# mcu.net
KiCad netlist of a schematic drawn in Altium Designer
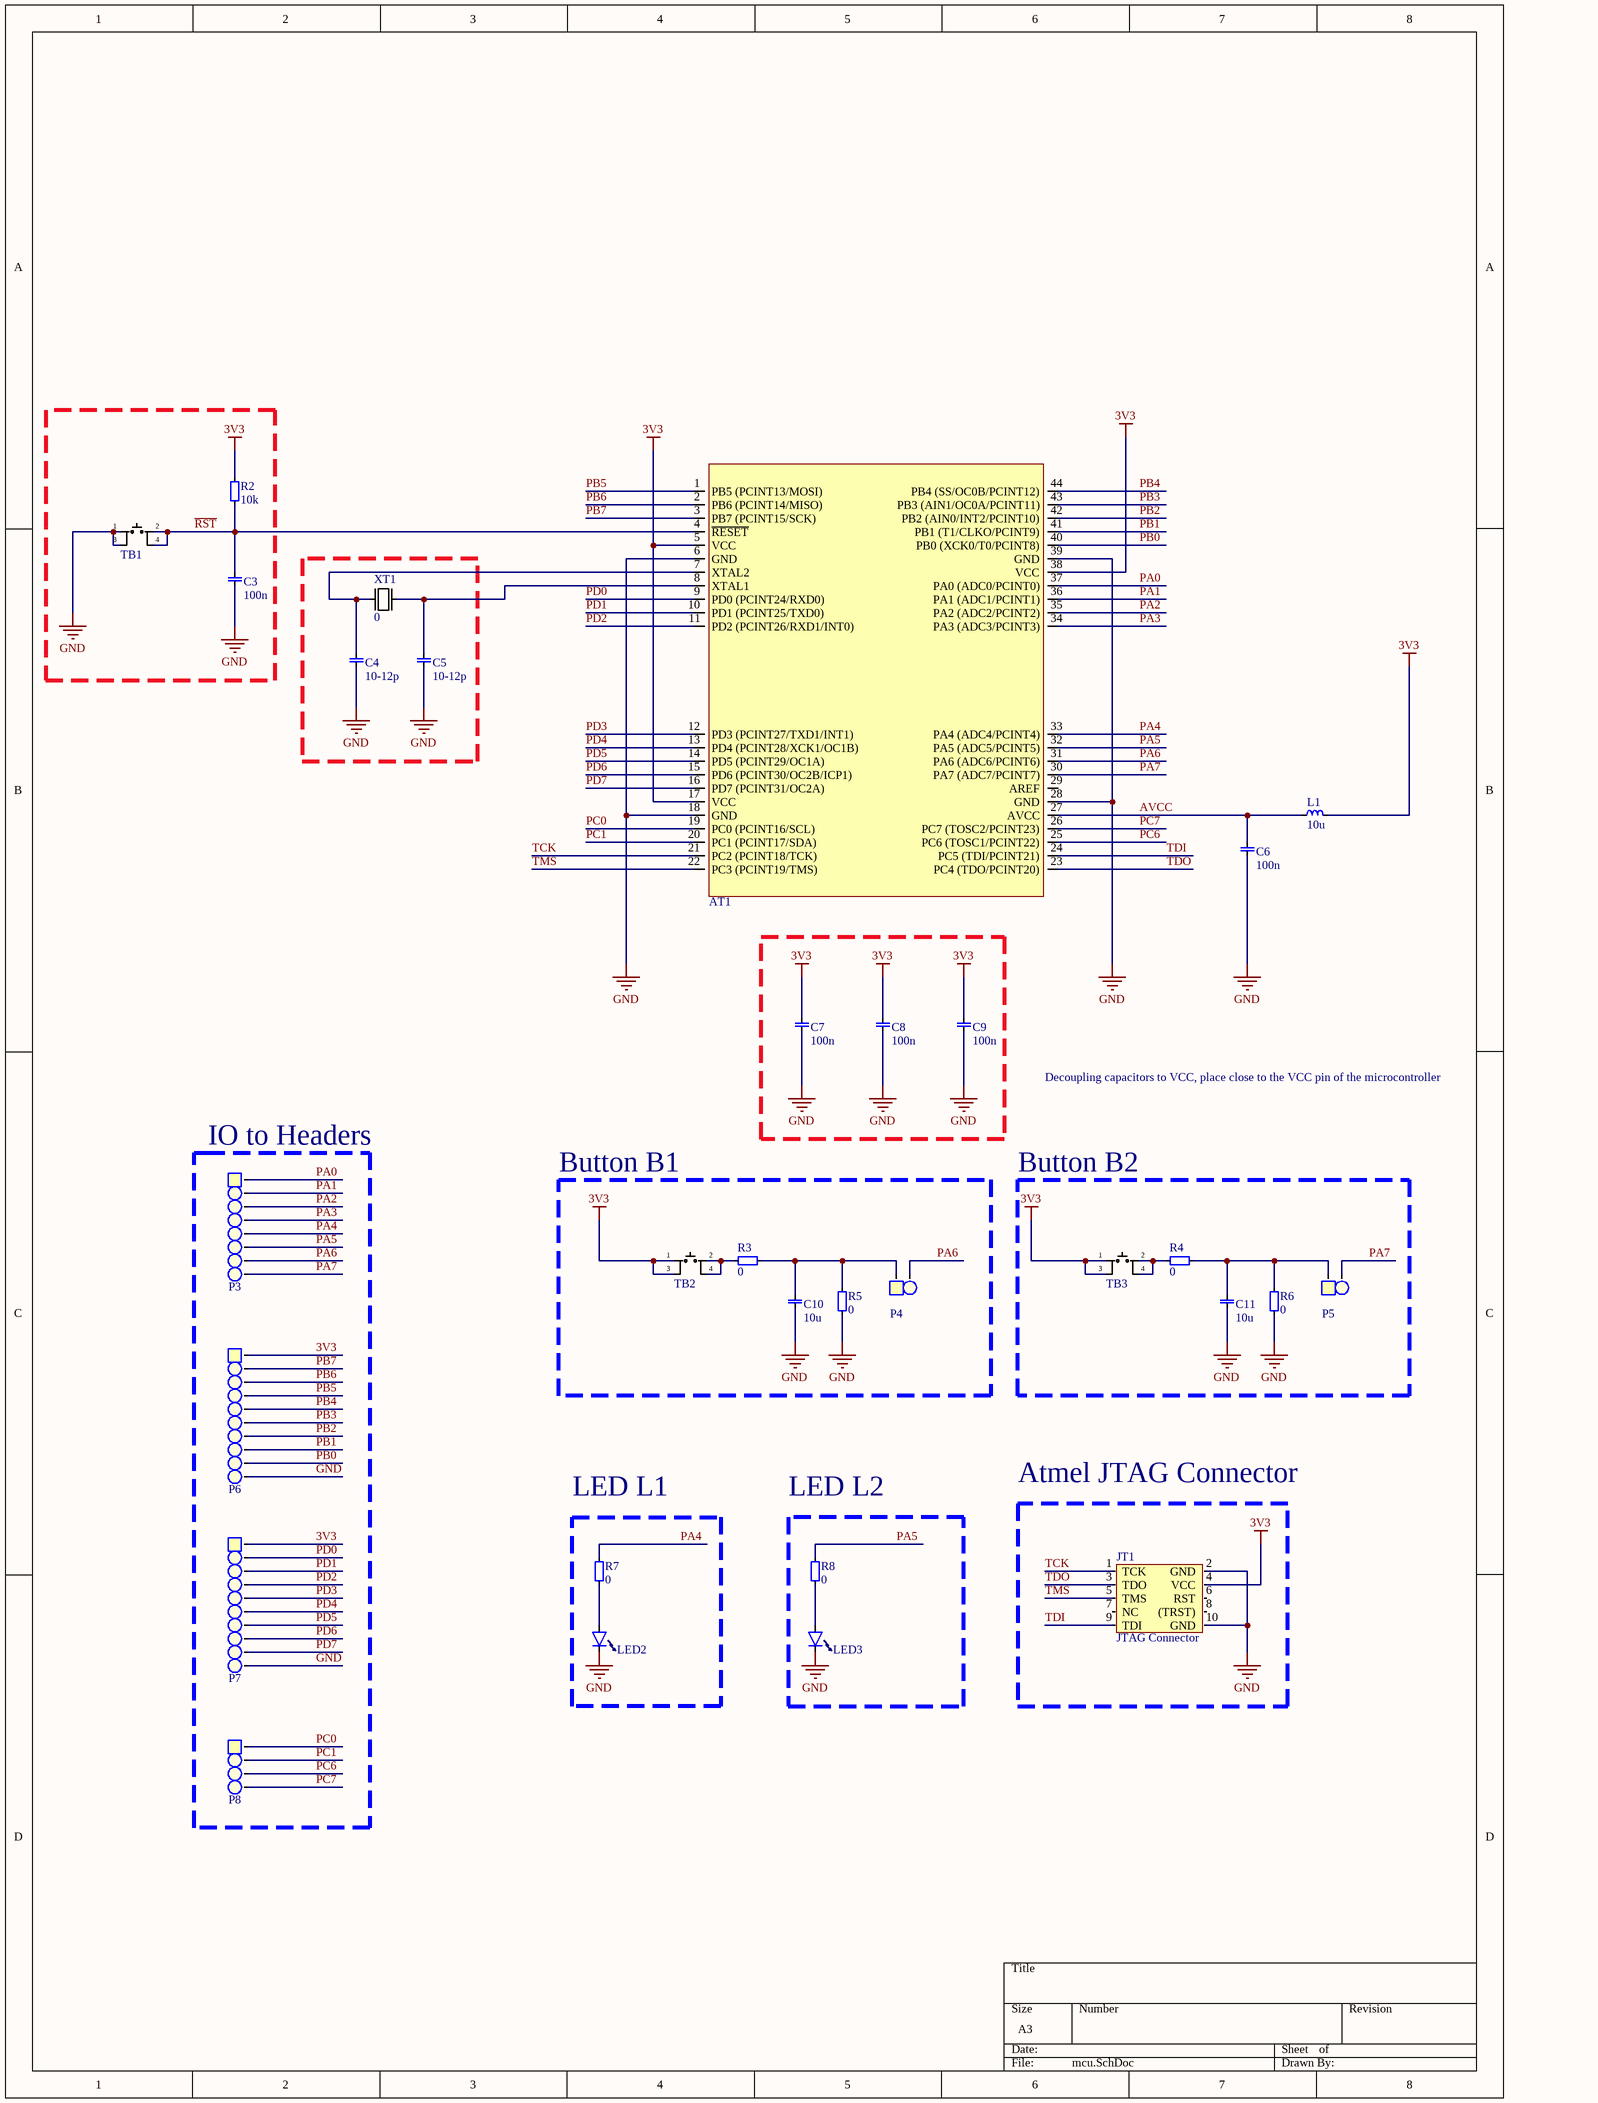
[diagram p0: mcu.SchDoc]

(export (version "E")
  (design (tool "Eeschema 10.0.6"))
  (components
    (comp (ref "AT1")
      (value "ATmega644PA")
      (footprint "TQFP-44")
      (description "ATmega644PA - Small but big and PicoPower")
      (libsource (lib "eitp15_lab1_lib") (part "ATmega644PA"))
    )
    (comp (ref "C3")
      (value "100n")
      (footprint "1206, capasitor")
      (fields (field (name "Comment") "1206, capacitor"))
      (libsource (lib "eitp15_lab1_lib") (part "1206, capacitor"))
    )
    (comp (ref "C4")
      (value "10-12p")
      (footprint "1206, capasitor")
      (fields (field (name "Comment") "1206, capacitor"))
      (libsource (lib "eitp15_lab1_lib") (part "1206, capacitor"))
    )
    (comp (ref "C5")
      (value "10-12p")
      (footprint "1206, capasitor")
      (fields (field (name "Comment") "1206, capacitor"))
      (libsource (lib "eitp15_lab1_lib") (part "1206, capacitor"))
    )
    (comp (ref "C6")
      (value "100n")
      (footprint "1206, capasitor")
      (fields (field (name "Comment") "1206, capacitor"))
      (libsource (lib "eitp15_lab1_lib") (part "1206, capacitor"))
    )
    (comp (ref "C7")
      (value "100n")
      (footprint "1206, capasitor")
      (fields (field (name "Comment") "1206, capacitor"))
      (libsource (lib "eitp15_lab1_lib") (part "1206, capacitor"))
    )
    (comp (ref "C8")
      (value "100n")
      (footprint "1206, capasitor")
      (fields (field (name "Comment") "1206, capacitor"))
      (libsource (lib "eitp15_lab1_lib") (part "1206, capacitor"))
    )
    (comp (ref "C9")
      (value "100n")
      (footprint "1206, capasitor")
      (fields (field (name "Comment") "1206, capacitor"))
      (libsource (lib "eitp15_lab1_lib") (part "1206, capacitor"))
    )
    (comp (ref "C10")
      (value "10u")
      (footprint "1206, capasitor")
      (fields (field (name "Comment") "1206, capacitor"))
      (libsource (lib "eitp15_lab1_lib") (part "1206, capacitor"))
    )
    (comp (ref "C11")
      (value "10u")
      (footprint "1206, capasitor")
      (fields (field (name "Comment") "1206, capacitor"))
      (libsource (lib "eitp15_lab1_lib") (part "1206, capacitor"))
    )
    (comp (ref "JT1")
      (value "JTAG Connector")
      (footprint "Atmel_JTAG")
      (description "Atmel JTAG Connector")
      (libsource (lib "eitp15_lab1_lib") (part "Atmel JTAG"))
    )
    (comp (ref "L1")
      (value "10u")
      (footprint "1812, coil")
      (fields (field (name "Comment") "Coil"))
      (libsource (lib "eitp15_lab1_lib") (part "Coil"))
    )
    (comp (ref "LED2")
      (value "0805, LED")
      (footprint "0805_led")
      (libsource (lib "eitp15_lab1_lib") (part "0805, LED"))
    )
    (comp (ref "LED3")
      (value "0805, LED")
      (footprint "0805_led")
      (libsource (lib "eitp15_lab1_lib") (part "0805, LED"))
    )
    (comp (ref "P3")
      (value "1x8 Pin Header")
      (footprint "1x8HEADER")
      (description "2.54 mm, TH")
      (libsource (lib "eitp15_lab1_lib") (part "1x8 Pin Header"))
    )
    (comp (ref "P4")
      (value "1x2 Pin Header")
      (footprint "1x2HEADER")
      (description "2.54 mm, TH")
      (libsource (lib "eitp15_lab1_lib") (part "1x2 Pin Header"))
    )
    (comp (ref "P5")
      (value "1x2 Pin Header")
      (footprint "1x2HEADER")
      (description "2.54 mm, TH")
      (libsource (lib "eitp15_lab1_lib") (part "1x2 Pin Header"))
    )
    (comp (ref "P6")
      (value "1x10 Pin Header")
      (footprint "1x10HEADER")
      (description "2.54 mm, TH")
      (libsource (lib "eitp15_lab1_lib") (part "1x10 Pin Header"))
    )
    (comp (ref "P7")
      (value "1x10 Pin Header")
      (footprint "1x10HEADER")
      (description "2.54 mm, TH")
      (libsource (lib "eitp15_lab1_lib") (part "1x10 Pin Header"))
    )
    (comp (ref "P8")
      (value "1x4 Pin Header")
      (footprint "1x4HEADER")
      (description "2.54 mm, TH")
      (libsource (lib "eitp15_lab1_lib") (part "1x4 Pin Header"))
    )
    (comp (ref "R2")
      (value "10k")
      (footprint "1206")
      (description "Resistor")
      (fields (field (name "Comment") "1206, resistor"))
      (libsource (lib "eitp15_lab1_lib") (part "1206, resistor"))
    )
    (comp (ref "R3")
      (value "0")
      (footprint "1206")
      (description "Resistor")
      (fields (field (name "Comment") "1206, resistor"))
      (libsource (lib "eitp15_lab1_lib") (part "1206, resistor"))
    )
    (comp (ref "R4")
      (value "0")
      (footprint "1206")
      (description "Resistor")
      (fields (field (name "Comment") "1206, resistor"))
      (libsource (lib "eitp15_lab1_lib") (part "1206, resistor"))
    )
    (comp (ref "R5")
      (value "0")
      (footprint "1206")
      (description "Resistor")
      (fields (field (name "Comment") "1206, resistor"))
      (libsource (lib "eitp15_lab1_lib") (part "1206, resistor"))
    )
    (comp (ref "R6")
      (value "0")
      (footprint "1206")
      (description "Resistor")
      (fields (field (name "Comment") "1206, resistor"))
      (libsource (lib "eitp15_lab1_lib") (part "1206, resistor"))
    )
    (comp (ref "R7")
      (value "0")
      (footprint "1206")
      (description "Resistor")
      (fields (field (name "Comment") "1206, resistor"))
      (libsource (lib "eitp15_lab1_lib") (part "1206, resistor"))
    )
    (comp (ref "R8")
      (value "0")
      (footprint "1206")
      (description "Resistor")
      (fields (field (name "Comment") "1206, resistor"))
      (libsource (lib "eitp15_lab1_lib") (part "1206, resistor"))
    )
    (comp (ref "TB1")
      (value "Tactile Button")
      (footprint "Button smd")
      (description "Tactile Switch Small Low")
      (libsource (lib "eitp15_lab1_lib") (part "Button SMD"))
    )
    (comp (ref "TB2")
      (value "Tactile Button")
      (footprint "Button smd")
      (description "Tactile Switch Small Low")
      (libsource (lib "eitp15_lab1_lib") (part "Button SMD"))
    )
    (comp (ref "TB3")
      (value "Tactile Button")
      (footprint "Button smd")
      (description "Tactile Switch Small Low")
      (libsource (lib "eitp15_lab1_lib") (part "Button SMD"))
    )
    (comp (ref "XT1")
      (value "0")
      (footprint "XTAL_SMD_LP")
      (description "16 MHz, SMD, 5mm x 3,2mm, 30 ppm")
      (fields (field (name "Comment") "XTAL TXC 7A"))
      (libsource (lib "eitp15_lab1_lib") (part "XTAL TXC 7A"))
    )
  )
  (nets
    (net (code "1") (name "/AVCC") (class "Default")
      (node (ref "AT1") (pin "27") (pinfunction "AVCC_27") (pintype "passive"))
      (node (ref "C6") (pin "1") (pinfunction "1_1") (pintype "passive"))
      (node (ref "L1") (pin "2") (pinfunction "2_2") (pintype "passive"))
    )
    (net (code "2") (name "/PA0") (class "Default")
      (node (ref "AT1") (pin "37") (pinfunction "PA0_(ADC0/PCINT0)_37") (pintype "passive"))
      (node (ref "P3") (pin "1") (pinfunction "1_1") (pintype "passive"))
    )
    (net (code "3") (name "/PA1") (class "Default")
      (node (ref "AT1") (pin "36") (pinfunction "PA1_(ADC1/PCINT1)_36") (pintype "passive"))
      (node (ref "P3") (pin "2") (pinfunction "2_2") (pintype "passive"))
    )
    (net (code "4") (name "/PA2") (class "Default")
      (node (ref "AT1") (pin "35") (pinfunction "PA2_(ADC2/PCINT2)_35") (pintype "passive"))
      (node (ref "P3") (pin "3") (pinfunction "3_3") (pintype "passive"))
    )
    (net (code "5") (name "/PA3") (class "Default")
      (node (ref "AT1") (pin "34") (pinfunction "PA3_(ADC3/PCINT3)_34") (pintype "passive"))
      (node (ref "P3") (pin "4") (pinfunction "4_4") (pintype "passive"))
    )
    (net (code "6") (name "/PA4") (class "Default")
      (node (ref "AT1") (pin "33") (pinfunction "PA4_(ADC4/PCINT4)_33") (pintype "passive"))
      (node (ref "P3") (pin "5") (pinfunction "5_5") (pintype "passive"))
      (node (ref "R7") (pin "0") (pinfunction "0_0") (pintype "passive"))
    )
    (net (code "7") (name "/PA5") (class "Default")
      (node (ref "AT1") (pin "32") (pinfunction "PA5_(ADC5/PCINT5)_32") (pintype "passive"))
      (node (ref "P3") (pin "6") (pinfunction "6_6") (pintype "passive"))
      (node (ref "R8") (pin "0") (pinfunction "0_0") (pintype "passive"))
    )
    (net (code "8") (name "/PA6") (class "Default")
      (node (ref "AT1") (pin "31") (pinfunction "PA6_(ADC6/PCINT6)_31") (pintype "passive"))
      (node (ref "P3") (pin "7") (pinfunction "7_7") (pintype "passive"))
      (node (ref "P4") (pin "2") (pinfunction "2_2") (pintype "passive"))
    )
    (net (code "9") (name "/PA7") (class "Default")
      (node (ref "AT1") (pin "30") (pinfunction "PA7_(ADC7/PCINT7)_30") (pintype "passive"))
      (node (ref "P3") (pin "8") (pinfunction "8_8") (pintype "passive"))
      (node (ref "P5") (pin "2") (pinfunction "2_2") (pintype "passive"))
    )
    (net (code "10") (name "/PB0") (class "Default")
      (node (ref "AT1") (pin "40") (pinfunction "PB0_(XCK0/T0/PCINT8)_40") (pintype "passive"))
      (node (ref "P6") (pin "9") (pinfunction "9_9") (pintype "passive"))
    )
    (net (code "11") (name "/PB1") (class "Default")
      (node (ref "AT1") (pin "41") (pinfunction "PB1_(T1/CLKO/PCINT9)_41") (pintype "passive"))
      (node (ref "P6") (pin "8") (pinfunction "8_8") (pintype "passive"))
    )
    (net (code "12") (name "/PB2") (class "Default")
      (node (ref "AT1") (pin "42") (pinfunction "PB2_(AIN0/INT2/PCINT10)_42") (pintype "passive"))
      (node (ref "P6") (pin "7") (pinfunction "7_7") (pintype "passive"))
    )
    (net (code "13") (name "/PB3") (class "Default")
      (node (ref "AT1") (pin "43") (pinfunction "PB3_(AIN1/OC0A/PCINT11)_43") (pintype "passive"))
      (node (ref "P6") (pin "6") (pinfunction "6_6") (pintype "passive"))
    )
    (net (code "14") (name "/PB4") (class "Default")
      (node (ref "AT1") (pin "44") (pinfunction "PB4_(SS/OC0B/PCINT12)_44") (pintype "passive"))
      (node (ref "P6") (pin "5") (pinfunction "5_5") (pintype "passive"))
    )
    (net (code "15") (name "/PB5") (class "Default")
      (node (ref "AT1") (pin "1") (pinfunction "PB5_(PCINT13/MOSI)_1") (pintype "passive"))
      (node (ref "P6") (pin "4") (pinfunction "4_4") (pintype "passive"))
    )
    (net (code "16") (name "/PB6") (class "Default")
      (node (ref "AT1") (pin "2") (pinfunction "PB6_(PCINT14/MISO)_2") (pintype "passive"))
      (node (ref "P6") (pin "3") (pinfunction "3_3") (pintype "passive"))
    )
    (net (code "17") (name "/PB7") (class "Default")
      (node (ref "AT1") (pin "3") (pinfunction "PB7_(PCINT15/SCK)_3") (pintype "passive"))
      (node (ref "P6") (pin "2") (pinfunction "2_2") (pintype "passive"))
    )
    (net (code "18") (name "/PC0") (class "Default")
      (node (ref "AT1") (pin "19") (pinfunction "PC0_(PCINT16/SCL)_19") (pintype "passive"))
      (node (ref "P8") (pin "1") (pinfunction "1_1") (pintype "passive"))
    )
    (net (code "19") (name "/PC1") (class "Default")
      (node (ref "AT1") (pin "20") (pinfunction "PC1_(PCINT17/SDA)_20") (pintype "passive"))
      (node (ref "P8") (pin "2") (pinfunction "2_2") (pintype "passive"))
    )
    (net (code "20") (name "/PC6") (class "Default")
      (node (ref "AT1") (pin "25") (pinfunction "PC6_(TOSC1/PCINT22)_25") (pintype "passive"))
      (node (ref "P8") (pin "3") (pinfunction "3_3") (pintype "passive"))
    )
    (net (code "21") (name "/PC7") (class "Default")
      (node (ref "AT1") (pin "26") (pinfunction "PC7_(TOSC2/PCINT23)_26") (pintype "passive"))
      (node (ref "P8") (pin "4") (pinfunction "4_4") (pintype "passive"))
    )
    (net (code "22") (name "/PD0") (class "Default")
      (node (ref "AT1") (pin "9") (pinfunction "PD0_(PCINT24/RXD0)_9") (pintype "passive"))
      (node (ref "P7") (pin "2") (pinfunction "2_2") (pintype "passive"))
    )
    (net (code "23") (name "/PD1") (class "Default")
      (node (ref "AT1") (pin "10") (pinfunction "PD1_(PCINT25/TXD0)_10") (pintype "passive"))
      (node (ref "P7") (pin "3") (pinfunction "3_3") (pintype "passive"))
    )
    (net (code "24") (name "/PD2") (class "Default")
      (node (ref "AT1") (pin "11") (pinfunction "PD2_(PCINT26/RXD1/INT0)_11") (pintype "passive"))
      (node (ref "P7") (pin "4") (pinfunction "4_4") (pintype "passive"))
    )
    (net (code "25") (name "/PD3") (class "Default")
      (node (ref "AT1") (pin "12") (pinfunction "PD3_(PCINT27/TXD1/INT1)_12") (pintype "passive"))
      (node (ref "P7") (pin "5") (pinfunction "5_5") (pintype "passive"))
    )
    (net (code "26") (name "/PD4") (class "Default")
      (node (ref "AT1") (pin "13") (pinfunction "PD4_(PCINT28/XCK1/OC1B)_13") (pintype "passive"))
      (node (ref "P7") (pin "6") (pinfunction "6_6") (pintype "passive"))
    )
    (net (code "27") (name "/PD5") (class "Default")
      (node (ref "AT1") (pin "14") (pinfunction "PD5_(PCINT29/OC1A)_14") (pintype "passive"))
      (node (ref "P7") (pin "7") (pinfunction "7_7") (pintype "passive"))
    )
    (net (code "28") (name "/PD6") (class "Default")
      (node (ref "AT1") (pin "15") (pinfunction "PD6_(PCINT30/OC2B/ICP1)_15") (pintype "passive"))
      (node (ref "P7") (pin "8") (pinfunction "8_8") (pintype "passive"))
    )
    (net (code "29") (name "/PD7") (class "Default")
      (node (ref "AT1") (pin "16") (pinfunction "PD7_(PCINT31/OC2A)_16") (pintype "passive"))
      (node (ref "P7") (pin "9") (pinfunction "9_9") (pintype "passive"))
    )
    (net (code "30") (name "/TCK") (class "Default")
      (node (ref "AT1") (pin "21") (pinfunction "PC2_(PCINT18/TCK)_21") (pintype "passive"))
      (node (ref "JT1") (pin "1") (pinfunction "TCK_1") (pintype "passive"))
    )
    (net (code "31") (name "/TDI") (class "Default")
      (node (ref "AT1") (pin "24") (pinfunction "PC5_(TDI/PCINT21)_24") (pintype "passive"))
      (node (ref "JT1") (pin "9") (pinfunction "TDI_9") (pintype "passive"))
    )
    (net (code "32") (name "/TDO") (class "Default")
      (node (ref "AT1") (pin "23") (pinfunction "PC4_(TDO/PCINT20)_23") (pintype "passive"))
      (node (ref "JT1") (pin "3") (pinfunction "TDO_3") (pintype "passive"))
    )
    (net (code "33") (name "/TMS") (class "Default")
      (node (ref "AT1") (pin "22") (pinfunction "PC3_(PCINT19/TMS)_22") (pintype "passive"))
      (node (ref "JT1") (pin "5") (pinfunction "TMS_5") (pintype "passive"))
    )
    (net (code "34") (name "/~{RST}") (class "Default")
      (node (ref "AT1") (pin "4") (pinfunction "~{RESET}_4") (pintype "passive"))
      (node (ref "C3") (pin "1") (pinfunction "1_1") (pintype "passive"))
      (node (ref "R2") (pin "1") (pinfunction "1_1") (pintype "passive"))
      (node (ref "TB1") (pin "2") (pinfunction "2_2") (pintype "passive"))
      (node (ref "TB1") (pin "4") (pinfunction "4_4") (pintype "passive"))
    )
    (net (code "35") (name "3V3") (class "Default")
      (node (ref "AT1") (pin "17") (pinfunction "VCC_17") (pintype "passive"))
      (node (ref "AT1") (pin "38") (pinfunction "VCC_38") (pintype "passive"))
      (node (ref "AT1") (pin "5") (pinfunction "VCC_5") (pintype "passive"))
      (node (ref "C7") (pin "1") (pinfunction "1_1") (pintype "passive"))
      (node (ref "C8") (pin "1") (pinfunction "1_1") (pintype "passive"))
      (node (ref "C9") (pin "1") (pinfunction "1_1") (pintype "passive"))
      (node (ref "JT1") (pin "4") (pinfunction "VCC_4") (pintype "passive"))
      (node (ref "L1") (pin "1") (pinfunction "1_1") (pintype "passive"))
      (node (ref "P6") (pin "1") (pinfunction "1_1") (pintype "passive"))
      (node (ref "P7") (pin "1") (pinfunction "1_1") (pintype "passive"))
      (node (ref "R2") (pin "0") (pinfunction "0_0") (pintype "passive"))
      (node (ref "TB2") (pin "1") (pinfunction "1_1") (pintype "passive"))
      (node (ref "TB2") (pin "3") (pinfunction "3_3") (pintype "passive"))
      (node (ref "TB3") (pin "1") (pinfunction "1_1") (pintype "passive"))
      (node (ref "TB3") (pin "3") (pinfunction "3_3") (pintype "passive"))
    )
    (net (code "36") (name "GND") (class "Default")
      (node (ref "AT1") (pin "18") (pinfunction "GND_18") (pintype "passive"))
      (node (ref "AT1") (pin "28") (pinfunction "GND_28") (pintype "passive"))
      (node (ref "AT1") (pin "39") (pinfunction "GND_39") (pintype "passive"))
      (node (ref "AT1") (pin "6") (pinfunction "GND_6") (pintype "passive"))
      (node (ref "C10") (pin "0") (pinfunction "0_0") (pintype "passive"))
      (node (ref "C11") (pin "0") (pinfunction "0_0") (pintype "passive"))
      (node (ref "C3") (pin "0") (pinfunction "0_0") (pintype "passive"))
      (node (ref "C4") (pin "0") (pinfunction "0_0") (pintype "passive"))
      (node (ref "C5") (pin "0") (pinfunction "0_0") (pintype "passive"))
      (node (ref "C6") (pin "0") (pinfunction "0_0") (pintype "passive"))
      (node (ref "C7") (pin "0") (pinfunction "0_0") (pintype "passive"))
      (node (ref "C8") (pin "0") (pinfunction "0_0") (pintype "passive"))
      (node (ref "C9") (pin "0") (pinfunction "0_0") (pintype "passive"))
      (node (ref "JT1") (pin "10") (pinfunction "GND_10") (pintype "passive"))
      (node (ref "JT1") (pin "2") (pinfunction "GND_2") (pintype "passive"))
      (node (ref "LED2") (pin "0") (pinfunction "Cathode_0") (pintype "passive"))
      (node (ref "LED3") (pin "0") (pinfunction "Cathode_0") (pintype "passive"))
      (node (ref "P6") (pin "10") (pinfunction "10_10") (pintype "passive"))
      (node (ref "P7") (pin "10") (pinfunction "10_10") (pintype "passive"))
      (node (ref "R5") (pin "1") (pinfunction "1_1") (pintype "passive"))
      (node (ref "R6") (pin "1") (pinfunction "1_1") (pintype "passive"))
      (node (ref "TB1") (pin "1") (pinfunction "1_1") (pintype "passive"))
      (node (ref "TB1") (pin "3") (pinfunction "3_3") (pintype "passive"))
    )
    (net (code "37") (name "Net-(AT1-XTAL1)") (class "Default")
      (node (ref "AT1") (pin "8") (pinfunction "XTAL1_8") (pintype "passive"))
      (node (ref "C5") (pin "1") (pinfunction "1_1") (pintype "passive"))
      (node (ref "XT1") (pin "2") (pinfunction "2_2") (pintype "passive"))
    )
    (net (code "38") (name "Net-(AT1-XTAL2)") (class "Default")
      (node (ref "AT1") (pin "7") (pinfunction "XTAL2_7") (pintype "passive"))
      (node (ref "C4") (pin "1") (pinfunction "1_1") (pintype "passive"))
      (node (ref "XT1") (pin "1") (pinfunction "1_1") (pintype "passive"))
    )
    (net (code "39") (name "Net-(C10-Pad1)") (class "Default")
      (node (ref "C10") (pin "1") (pinfunction "1_1") (pintype "passive"))
      (node (ref "P4") (pin "1") (pinfunction "1_1") (pintype "passive"))
      (node (ref "R3") (pin "0") (pinfunction "0_0") (pintype "passive"))
      (node (ref "R5") (pin "0") (pinfunction "0_0") (pintype "passive"))
    )
    (net (code "40") (name "Net-(C11-Pad1)") (class "Default")
      (node (ref "C11") (pin "1") (pinfunction "1_1") (pintype "passive"))
      (node (ref "P5") (pin "1") (pinfunction "1_1") (pintype "passive"))
      (node (ref "R4") (pin "0") (pinfunction "0_0") (pintype "passive"))
      (node (ref "R6") (pin "0") (pinfunction "0_0") (pintype "passive"))
    )
    (net (code "41") (name "Net-(LED2-Pad1)") (class "Default")
      (node (ref "LED2") (pin "1") (pinfunction "1_1") (pintype "passive"))
      (node (ref "R7") (pin "1") (pinfunction "1_1") (pintype "passive"))
    )
    (net (code "42") (name "Net-(LED3-Pad1)") (class "Default")
      (node (ref "LED3") (pin "1") (pinfunction "1_1") (pintype "passive"))
      (node (ref "R8") (pin "1") (pinfunction "1_1") (pintype "passive"))
    )
    (net (code "43") (name "Net-(R3-Pad1)") (class "Default")
      (node (ref "R3") (pin "1") (pinfunction "1_1") (pintype "passive"))
      (node (ref "TB2") (pin "2") (pinfunction "2_2") (pintype "passive"))
      (node (ref "TB2") (pin "4") (pinfunction "4_4") (pintype "passive"))
    )
    (net (code "44") (name "Net-(R4-Pad1)") (class "Default")
      (node (ref "R4") (pin "1") (pinfunction "1_1") (pintype "passive"))
      (node (ref "TB3") (pin "2") (pinfunction "2_2") (pintype "passive"))
      (node (ref "TB3") (pin "4") (pinfunction "4_4") (pintype "passive"))
    )
    (net (code "45") (name "unconnected-(AT1-AREF-Pad29)") (class "Default")
      (node (ref "AT1") (pin "29") (pinfunction "AREF_29") (pintype "passive"))
    )
    (net (code "46") (name "unconnected-(JT1-(TRST)-Pad8)") (class "Default")
      (node (ref "JT1") (pin "8") (pinfunction "(TRST)_8") (pintype "passive"))
    )
    (net (code "47") (name "unconnected-(JT1-NC-Pad7)") (class "Default")
      (node (ref "JT1") (pin "7") (pinfunction "NC_7") (pintype "passive"))
    )
    (net (code "48") (name "unconnected-(JT1-RST-Pad6)") (class "Default")
      (node (ref "JT1") (pin "6") (pinfunction "RST_6") (pintype "passive"))
    )
  )
)
